# NuPrism_MCPMT_-_ADA4945-1_and_Filter_-_R.net
KiCad netlist of a schematic drawn in Altium Designer
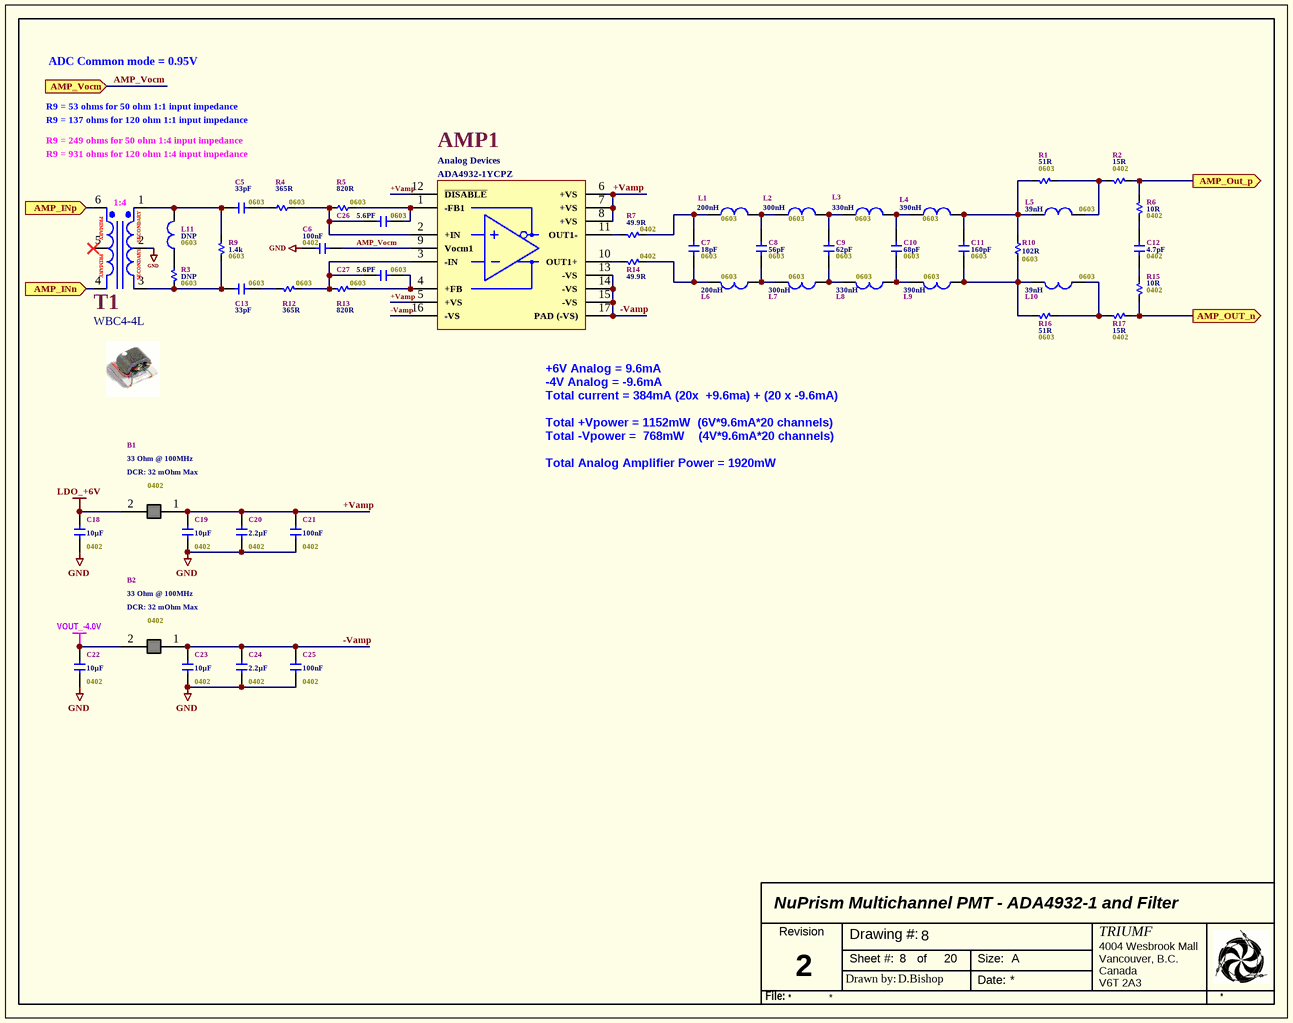
[diagram p0: NuPrism_MCPMT - ADA4945-1 and Filter - Rev2.SchDoc]

(export (version "E")
  (design (tool "Eeschema 10.0.6"))
  (components
    (comp (ref "AMP1")
      (value "ADA4932-1YCPZ")
      (footprint "QFN50P300X300X100-16N_ALT")
      (description "High Speed, ±0.1 µV/˚C Offset Drift, Fully Differential ADC Driver")
      (fields (field (name "MANUFACTURER") "Analog Devices") (field (name "PARTNO") "ADA4932-1YCPZ"))
      (libsource (lib "NuPrism_MCPMT") (part "ADA4932-1YCPZ_ALT"))
    )
    (comp (ref "B1")
      (value "BLM15PX600SN1D")
      (footprint "0402")
      (description "60 Ohms @ 100MHz Ferrite Bead 0402 2.5A")
      (fields
        (field (name "MANUFACTURER") "Murata")
        (field (name "DCR") "32 mOhm Max")
        (field (name "IMPEDANCE @ FREQUENCY") "33 Ohm @ 100MHz")
        (field (name "PACKAGE") "0402")
      )
      (libsource (lib "Clock Distribution Module") (part "Ferrite Bead"))
    )
    (comp (ref "B2")
      (value "BLM15PX600SN1D")
      (footprint "0402")
      (description "60 Ohms @ 100MHz Ferrite Bead 0402 2.5A")
      (fields
        (field (name "MANUFACTURER") "Murata")
        (field (name "DCR") "32 mOhm Max")
        (field (name "IMPEDANCE @ FREQUENCY") "33 Ohm @ 100MHz")
        (field (name "PACKAGE") "0402")
      )
      (libsource (lib "Clock Distribution Module") (part "Ferrite Bead"))
    )
    (comp (ref "C5")
      (value "C0603C330J1GAC7867")
      (footprint "0603")
      (description "33 pF ±5% 100V Ceramic Capacitor C0G, NP0 0603")
      (fields
        (field (name "MANUFACTURER") "KEMET")
        (field (name "CAPACITANCE") "33pF")
        (field (name "PACKAGE") "0603")
        (field (name "VOLTAGE") "100V")
      )
      (libsource (lib "altium-import") (part "root_1_CAP-SMALL_"))
    )
    (comp (ref "C6")
      (value "C0402C104K4RACTU")
      (footprint "0402")
      (description "SMD/SMT 0402 16V 0.1uF X7R 10%")
      (fields
        (field (name "MANUFACTURER") "Kemet")
        (field (name "CAPACITANCE") "100nF")
        (field (name "PACKAGE") "0402")
        (field (name "VOLTAGE") "16V")
      )
      (libsource (lib "NuPrism_MCPMT") (part "CAP-SMALL"))
    )
    (comp (ref "C7")
      (value "CC0603JPNPO9BN180")
      (footprint "0603")
      (description "18 pF ±5% 50V Ceramic Capacitor C0G, NP0 0603")
      (fields
        (field (name "CAPACITANCE") "18pF")
        (field (name "PACKAGE") "0603")
        (field (name "MANUFACTURER") "Yageo")
        (field (name "VOLTAGE") "50V")
      )
      (libsource (lib "") (part "root_2_CAP-SMALL__1"))
    )
    (comp (ref "C8")
      (value "C0603C560J5GAC7867")
      (footprint "0603")
      (description "56 pF ±5% 50V Ceramic Capacitor C0G, NP0 0603 (1608 Metric)")
      (fields
        (field (name "MANUFACTURER") "KEMET")
        (field (name "CAPACITANCE") "56pF")
        (field (name "PACKAGE") "0603")
        (field (name "VOLTAGE") "50V")
      )
      (libsource (lib "") (part "root_2_CAP-SMALL__1"))
    )
    (comp (ref "C9")
      (value "CC0603JRNPO9BN620")
      (footprint "0603")
      (description "62 pF ±5% 50V Ceramic Capacitor C0G, NP0 0603 (1608 Metric)")
      (fields
        (field (name "MANUFACTURER") "YAGEO")
        (field (name "CAPACITANCE") "62pF")
        (field (name "PACKAGE") "0603")
        (field (name "VOLTAGE") "50V")
      )
      (libsource (lib "") (part "root_2_CAP-SMALL__1"))
    )
    (comp (ref "C10")
      (value "CC0603JRNPO9BN680")
      (footprint "0603")
      (description "CAP CER 68PF 50V C0G/NPO 0603 (1608 Metric)")
      (fields
        (field (name "CAPACITANCE") "68pF")
        (field (name "PACKAGE") "0603")
        (field (name "MANUFACTURER") "Yageo")
        (field (name "VOLTAGE") "50V")
      )
      (libsource (lib "") (part "root_2_CAP-SMALL__1"))
    )
    (comp (ref "C11")
      (value "CC0603JRNPO9BN161")
      (footprint "0603")
      (description "160 pF ±5% 50V Ceramic Capacitor C0G, NP0 0603 (1608 Metric)")
      (fields
        (field (name "MANUFACTURER") "YAGEO")
        (field (name "CAPACITANCE") "160pF")
        (field (name "PACKAGE") "0603")
        (field (name "VOLTAGE") "50V")
      )
      (libsource (lib "") (part "root_2_CAP-SMALL__1"))
    )
    (comp (ref "C12")
      (value "CC0402BRNPO9BN4R7")
      (footprint "0402")
      (description "4.7pF ±0.1pF 50V Ceramic Capacitor C0G, NP0 0402")
      (fields
        (field (name "MANUFACTURER") "Yageo")
        (field (name "CAPACITANCE") "4.7pF")
        (field (name "PACKAGE") "0402")
        (field (name "VOLTAGE") "50V")
      )
      (libsource (lib "") (part "root_2_CAP-SMALL__1"))
    )
    (comp (ref "C13")
      (value "C0603C330J1GAC7867")
      (footprint "0603")
      (description "33 pF ±5% 100V Ceramic Capacitor C0G, NP0 0603")
      (fields
        (field (name "MANUFACTURER") "KEMET")
        (field (name "CAPACITANCE") "33pF")
        (field (name "PACKAGE") "0603")
        (field (name "VOLTAGE") "100V")
      )
      (libsource (lib "altium-import") (part "root_3_mirrored_CAP-SMALL_"))
    )
    (comp (ref "C18")
      (value "CL05A106MQ5NRNC")
      (footprint "0402")
      (description "10 µF ±20% 6.3V Ceramic Capacitor X5R 0402 (1005 Metric)")
      (fields
        (field (name "CAPACITANCE") "10µF")
        (field (name "PACKAGE") "0402")
        (field (name "MANUFACTURER") "Samsung Electro-Mechanics")
        (field (name "VOLTAGE") "6.3V")
      )
      (libsource (lib "altium-import") (part "root_2_CAP-SMALL_"))
    )
    (comp (ref "C19")
      (value "CL05A106MQ5NRNC")
      (footprint "0402")
      (description "10 µF ±20% 6.3V Ceramic Capacitor X5R 0402 (1005 Metric)")
      (fields
        (field (name "CAPACITANCE") "10µF")
        (field (name "PACKAGE") "0402")
        (field (name "MANUFACTURER") "Samsung Electro-Mechanics")
        (field (name "VOLTAGE") "6.3V")
      )
      (libsource (lib "altium-import") (part "root_2_CAP-SMALL_"))
    )
    (comp (ref "C20")
      (value "TMK105CBJ225KV-F")
      (footprint "0402")
      (description "SMD/SMT 0402 25V 2.2uF 10% X5R")
      (fields
        (field (name "MANUFACTURER") "Taiyo Yuden")
        (field (name "CAPACITANCE") "2.2µF")
        (field (name "PACKAGE") "0402")
        (field (name "VOLTAGE") "25V")
      )
      (libsource (lib "altium-import") (part "root_0_CAP-SMALL_"))
    )
    (comp (ref "C21")
      (value "C0402C104K4RACTU")
      (footprint "0402")
      (description "SMD/SMT 0402 16V 0.1uF X7R 10%")
      (fields
        (field (name "MANUFACTURER") "Kemet")
        (field (name "CAPACITANCE") "100nF")
        (field (name "PACKAGE") "0402")
        (field (name "VOLTAGE") "16V")
      )
      (libsource (lib "NuPrism_MCPMT") (part "CAP-SMALL"))
    )
    (comp (ref "C22")
      (value "CL05A106MQ5NRNC")
      (footprint "0402")
      (description "10 µF ±20% 6.3V Ceramic Capacitor X5R 0402 (1005 Metric)")
      (fields
        (field (name "CAPACITANCE") "10µF")
        (field (name "PACKAGE") "0402")
        (field (name "MANUFACTURER") "Samsung Electro-Mechanics")
        (field (name "VOLTAGE") "6.3V")
      )
      (libsource (lib "altium-import") (part "root_2_CAP-SMALL_"))
    )
    (comp (ref "C23")
      (value "CL05A106MQ5NRNC")
      (footprint "0402")
      (description "10 µF ±20% 6.3V Ceramic Capacitor X5R 0402 (1005 Metric)")
      (fields
        (field (name "CAPACITANCE") "10µF")
        (field (name "PACKAGE") "0402")
        (field (name "MANUFACTURER") "Samsung Electro-Mechanics")
        (field (name "VOLTAGE") "6.3V")
      )
      (libsource (lib "altium-import") (part "root_2_CAP-SMALL_"))
    )
    (comp (ref "C24")
      (value "TMK105CBJ225KV-F")
      (footprint "0402")
      (description "SMD/SMT 0402 25V 2.2uF 10% X5R")
      (fields
        (field (name "MANUFACTURER") "Taiyo Yuden")
        (field (name "CAPACITANCE") "2.2µF")
        (field (name "PACKAGE") "0402")
        (field (name "VOLTAGE") "25V")
      )
      (libsource (lib "altium-import") (part "root_0_CAP-SMALL_"))
    )
    (comp (ref "C25")
      (value "C0402C104K4RACTU")
      (footprint "0402")
      (description "SMD/SMT 0402 16V 0.1uF X7R 10%")
      (fields
        (field (name "MANUFACTURER") "Kemet")
        (field (name "CAPACITANCE") "100nF")
        (field (name "PACKAGE") "0402")
        (field (name "VOLTAGE") "16V")
      )
      (libsource (lib "NuPrism_MCPMT") (part "CAP-SMALL"))
    )
    (comp (ref "C26")
      (value "06035A5R6JAT2A")
      (footprint "0603")
      (description "5.6 pF ±5% 50V Ceramic Capacitor C0G, NP0 0603")
      (fields
        (field (name "MANUFACTURER") "KYOCERA AVX")
        (field (name "CAPACITANCE") "5.6PF")
        (field (name "PACKAGE") "0603")
        (field (name "VOLTAGE") "50V")
      )
      (libsource (lib "altium-import") (part "root_3_CAP-SMALL_"))
    )
    (comp (ref "C27")
      (value "06035A5R6JAT2A")
      (footprint "0603")
      (description "5.6 pF ±5% 50V Ceramic Capacitor C0G, NP0 0603")
      (fields
        (field (name "MANUFACTURER") "KYOCERA AVX")
        (field (name "CAPACITANCE") "5.6PF")
        (field (name "PACKAGE") "0603")
        (field (name "VOLTAGE") "50V")
      )
      (libsource (lib "altium-import") (part "root_3_CAP-SMALL_"))
    )
    (comp (ref "L1")
      (value "LQW18ANR20J8ZD")
      (footprint "NumPrism Mutichannel PMT:0603 - Inductor")
      (description "200 nH Unshielded Wirewound Inductor 120 mA 2.40Ohm Max 0603")
      (fields
        (field (name "PACKAGE") "0603")
        (field (name "INDUCTANCE") "200nH")
        (field (name "MANUFACTURER") "Murata Electronics")
        (field (name "PARTNO") "LQW18ANR20G00D")
      )
      (libsource (lib "NuPrism - mPMT") (part "Inductor1"))
    )
    (comp (ref "L2")
      (value "LQW18ANR30G80D")
      (footprint "0603 - Inductor")
      (description "300 nH Unshielded Wirewound Inductor 220 mA 3.12Ohm Max 0603")
      (fields
        (field (name "PACKAGE") "0603")
        (field (name "INDUCTANCE") "300nH")
        (field (name "MANUFACTURER") "Coilcraft")
        (field (name "PARTNO") "LQW18ANR30G8ZD")
      )
      (libsource (lib "NuPrism - mPMT") (part "Inductor1"))
    )
    (comp (ref "L3")
      (value "LQW18CNR33J00D")
      (footprint "0603 - Inductor")
      (description "330 nH Unshielded Drum Core, Wirewound Inductor 630 mA 250mOhm Max 0603")
      (fields
        (field (name "PACKAGE") "0603")
        (field (name "INDUCTANCE") "330nH")
        (field (name "MANUFACTURER") "Murata Electronics")
      )
      (libsource (lib "NuPrism - mPMT") (part "Inductor1"))
    )
    (comp (ref "L4")
      (value "MLJ1608WR39JT000")
      (footprint "0603 - inductor")
      (description "390 nH Shielded Multilayer Inductor 450 mA 364mOhm Max 0603 (1608 Metric)")
      (fields
        (field (name "PACKAGE") "0603")
        (field (name "INDUCTANCE") "390nH")
        (field (name "MANUFACTURER") "TDK Corporation")
      )
      (libsource (lib "NuPrism - mPMT") (part "Inductor1"))
    )
    (comp (ref "L5")
      (value "LQW18AN39NJ00D")
      (footprint "0603 - Inductor_2")
      (description "39 nH Unshielded Wirewound Inductor 400 mA 260mOhm Max 0603 (1608 Metric)")
      (fields
        (field (name "PACKAGE") "0603")
        (field (name "INDUCTANCE") "39nH")
        (field (name "MANUFACTURER") "Murata Electronics")
      )
      (libsource (lib "NuPrism - mPMT") (part "Inductor1"))
    )
    (comp (ref "L6")
      (value "LQW18ANR20J8ZD")
      (footprint "0603 - Inductor")
      (description "200 nH Unshielded Wirewound Inductor 120 mA 2.40Ohm Max 0603")
      (fields
        (field (name "PACKAGE") "0603")
        (field (name "INDUCTANCE") "200nH")
        (field (name "MANUFACTURER") "Murata Electronics")
        (field (name "PARTNO") "LQW18ANR20G00D")
      )
      (libsource (lib "") (part "Inductor1_1"))
    )
    (comp (ref "L7")
      (value "LQW18ANR30G80D")
      (footprint "0603 - Inductor")
      (description "300 nH Unshielded Wirewound Inductor 220 mA 3.12Ohm Max 0603")
      (fields
        (field (name "PACKAGE") "0603")
        (field (name "INDUCTANCE") "300nH")
        (field (name "MANUFACTURER") "Coilcraft")
        (field (name "PARTNO") "LQW18ANR30G8ZD")
      )
      (libsource (lib "") (part "Inductor1_1"))
    )
    (comp (ref "L8")
      (value "LQW18CNR33J00D")
      (footprint "0603 - Inductor")
      (description "330 nH Unshielded Drum Core, Wirewound Inductor 630 mA 250mOhm Max 0603")
      (fields
        (field (name "PACKAGE") "0603")
        (field (name "INDUCTANCE") "330nH")
        (field (name "MANUFACTURER") "Murata Electronics")
      )
      (libsource (lib "") (part "Inductor1_1"))
    )
    (comp (ref "L9")
      (value "MLJ1608WR39JT000")
      (footprint "0603 - inductor")
      (description "390 nH Shielded Multilayer Inductor 450 mA 364mOhm Max 0603 (1608 Metric)")
      (fields
        (field (name "PACKAGE") "0603")
        (field (name "INDUCTANCE") "390nH")
        (field (name "MANUFACTURER") "TDK Corporation")
      )
      (libsource (lib "") (part "Inductor1_1"))
    )
    (comp (ref "L10")
      (value "LQW18AN39NJ00D")
      (footprint "0603 - Inductor_2")
      (description "39 nH Unshielded Wirewound Inductor 400 mA 260mOhm Max 0603 (1608 Metric)")
      (fields
        (field (name "PACKAGE") "0603")
        (field (name "INDUCTANCE") "39nH")
        (field (name "MANUFACTURER") "Murata Electronics")
      )
      (libsource (lib "") (part "Inductor1_1"))
    )
    (comp (ref "L11")
      (value "~")
      (footprint "0603 - Inductor")
      (description "Do not put")
      (fields (field (name "PACKAGE") "0603") (field (name "INDUCTANCE") "DNP"))
      (libsource (lib "NuPrism - mPMT") (part "Inductor1"))
    )
    (comp (ref "R1")
      (value "RC0603FR-0751RL")
      (footprint "0603")
      (description "Thick Film Resistors - SMD 51 OHM 1%")
      (fields
        (field (name "MANUFACTURER") "Yageo")
        (field (name "RESISTANCE") "51R")
        (field (name "PACKAGE") "0603")
      )
      (libsource (lib "NuPrism - mPMT") (part "RES-TINY"))
    )
    (comp (ref "R2")
      (value "RMCF0402FT15R0")
      (footprint "0402")
      (description "15 Ohms ±1% 0.063W, 1/16W Chip Resistor 0402 (1005 Metric)")
      (fields
        (field (name "MANUFACTURER") "Stackpole Electronics Inc")
        (field (name "RESISTANCE") "15R")
        (field (name "PACKAGE") "0402")
      )
      (libsource (lib "NuPrism - mPMT") (part "RES-TINY"))
    )
    (comp (ref "R3")
      (value "~")
      (footprint "0603")
      (description "Do not put")
      (fields
        (field (name "MANUFACTURER") "Yageo")
        (field (name "PARTNO") "RT0603BRD07820RL")
        (field (name "RESISTANCE") "DNP")
        (field (name "PACKAGE") "0603")
      )
      (libsource (lib "NuPrism - mPMT") (part "RES-TINY"))
    )
    (comp (ref "R4")
      (value "ERJ-PB3B3650V")
      (footprint "0603")
      (description "Thick Film Resistors - SMD 0603 Anti-Surge Res. 0.1%, 365ohm")
      (fields
        (field (name "MANUFACTURER") "Panasonic")
        (field (name "RESISTANCE") "365R")
        (field (name "PACKAGE") "0603")
      )
      (libsource (lib "NuPrism - mPMT") (part "RES-TINY"))
    )
    (comp (ref "R5")
      (value "RT0603BRD07820RL")
      (footprint "0603")
      (description "820 Ohms ±0.1% 0.1W, 1/10W Chip Resistor 0603 (1608 Metric) Thin Film")
      (fields
        (field (name "MANUFACTURER") "Yageo")
        (field (name "RESISTANCE") "820R")
        (field (name "PACKAGE") "0603")
      )
      (libsource (lib "NuPrism - mPMT") (part "RES-TINY"))
    )
    (comp (ref "R6")
      (value "RC0402FR-0710RL")
      (footprint "0402")
      (description "10 Ohms ±1% 0.063W, 1/16W Chip Resistor 0402")
      (fields
        (field (name "MANUFACTURER") "Yageo")
        (field (name "RESISTANCE") "10R")
        (field (name "PACKAGE") "0402")
        (field (name "VOLTAGE") "50V")
      )
      (libsource (lib "") (part "RES-TINY_2"))
    )
    (comp (ref "R7")
      (value "RMCF0402FT49R9")
      (footprint "0402")
      (description "49.9 Ohms ±1% 0.063W, 1/16W Chip Resistor 0402 (1005 Metric)")
      (fields
        (field (name "MANUFACTURER") "Stackpole Electronics Inc")
        (field (name "RESISTANCE") "49.9R")
        (field (name "PACKAGE") "0402")
      )
      (libsource (lib "NuPrism - mPMT") (part "RES-TINY"))
    )
    (comp (ref "R9")
      (value "RC0603FR-101K4L")
      (footprint "0603")
      (description "1.4 kOhms ±1% 0.1W, 1/10W Chip Resistor 0603 (1608 Metric) Thick Film")
      (fields
        (field (name "MANUFACTURER") "Stackpole")
        (field (name "PARTNO") "RC0603FR-101K2L")
        (field (name "RESISTANCE") "1.4k")
        (field (name "PACKAGE") "0603")
      )
      (libsource (lib "NuPrism - mPMT") (part "RES-TINY"))
    )
    (comp (ref "R10")
      (value "RC0603FR-07102RL")
      (footprint "0603")
      (description "102 Ohms ±1% 0.1W, 1/10W Chip Resistor 0603")
      (fields
        (field (name "MANUFACTURER") "Yageo")
        (field (name "RESISTANCE") "102R")
        (field (name "PACKAGE") "0603")
      )
      (libsource (lib "NuPrism - mPMT") (part "RES-TINY"))
    )
    (comp (ref "R12")
      (value "ERJ-PB3B3650V")
      (footprint "0603")
      (description "Thick Film Resistors - SMD 0603 Anti-Surge Res. 0.1%, 365ohm")
      (fields
        (field (name "MANUFACTURER") "Panasonic")
        (field (name "RESISTANCE") "365R")
        (field (name "PACKAGE") "0603")
      )
      (libsource (lib "NuPrism - mPMT") (part "RES-TINY"))
    )
    (comp (ref "R13")
      (value "RT0603BRD07820RL")
      (footprint "0603")
      (description "820 Ohms ±0.1% 0.1W, 1/10W Chip Resistor 0603 (1608 Metric) Thin Film")
      (fields
        (field (name "MANUFACTURER") "Yageo")
        (field (name "RESISTANCE") "820R")
        (field (name "PACKAGE") "0603")
      )
      (libsource (lib "NuPrism - mPMT") (part "RES-TINY"))
    )
    (comp (ref "R14")
      (value "RMCF0402FT49R9")
      (footprint "0402")
      (description "49.9 Ohms ±1% 0.063W, 1/16W Chip Resistor 0402 (1005 Metric)")
      (fields
        (field (name "MANUFACTURER") "Stackpole Electronics Inc")
        (field (name "RESISTANCE") "49.9R")
        (field (name "PACKAGE") "0402")
      )
      (libsource (lib "NuPrism - mPMT") (part "RES-TINY"))
    )
    (comp (ref "R15")
      (value "RC0402FR-0710RL")
      (footprint "0402")
      (description "10 Ohms ±1% 0.063W, 1/16W Chip Resistor 0402")
      (fields
        (field (name "MANUFACTURER") "Yageo")
        (field (name "RESISTANCE") "10R")
        (field (name "PACKAGE") "0402")
        (field (name "VOLTAGE") "50V")
      )
      (libsource (lib "") (part "RES-TINY_1"))
    )
    (comp (ref "R16")
      (value "RC0603FR-0751RL")
      (footprint "0603")
      (description "Thick Film Resistors - SMD 51 OHM 1%")
      (fields
        (field (name "MANUFACTURER") "Yageo")
        (field (name "RESISTANCE") "51R")
        (field (name "PACKAGE") "0603")
      )
      (libsource (lib "NuPrism - mPMT") (part "RES-TINY"))
    )
    (comp (ref "R17")
      (value "RMCF0402FT15R0")
      (footprint "0402")
      (description "15 Ohms ±1% 0.063W, 1/16W Chip Resistor 0402 (1005 Metric)")
      (fields
        (field (name "MANUFACTURER") "Stackpole Electronics Inc")
        (field (name "RESISTANCE") "15R")
        (field (name "PACKAGE") "0402")
      )
      (libsource (lib "NuPrism - mPMT") (part "RES-TINY"))
    )
    (comp (ref "T1")
      (value "WBC4-4L")
      (footprint "WBC4-4WL")
      (description "Audio Transformers / Signal Transformers WBC SMT Mini Wdebnd 1:4 0.250-800 MHz")
      (fields (field (name "MANUFACTURER") "Coilcraft"))
      (libsource (lib "NuPrism_MCPMT") (part "WBC4-4L"))
    )
  )
  (nets
    (net (code "1") (name "/+Vamp") (class "Default")
      (node (ref "AMP1") (pin "12") (pinfunction "~{DISABLE}_12") (pintype "passive"))
      (node (ref "AMP1") (pin "5") (pinfunction "+VS_5") (pintype "power_in"))
      (node (ref "AMP1") (pin "6") (pinfunction "+VS_6") (pintype "power_in"))
      (node (ref "AMP1") (pin "7") (pinfunction "+VS_7") (pintype "power_in"))
      (node (ref "AMP1") (pin "8") (pinfunction "+VS_8") (pintype "power_in"))
      (node (ref "B1") (pin "1") (pinfunction "1_1") (pintype "passive"))
      (node (ref "C19") (pin "2") (pintype "passive"))
      (node (ref "C20") (pin "1") (pintype "passive"))
      (node (ref "C21") (pin "1") (pintype "passive"))
    )
    (net (code "2") (name "/-Vamp") (class "Default")
      (node (ref "AMP1") (pin "13") (pinfunction "-VS_13") (pintype "power_in"))
      (node (ref "AMP1") (pin "14") (pinfunction "-VS_14") (pintype "power_in"))
      (node (ref "AMP1") (pin "15") (pinfunction "-VS_15") (pintype "power_in"))
      (node (ref "AMP1") (pin "16") (pinfunction "-VS_16") (pintype "power_in"))
      (node (ref "AMP1") (pin "17") (pinfunction "PAD_(-VS)_17") (pintype "power_in"))
      (node (ref "B2") (pin "1") (pinfunction "1_1") (pintype "passive"))
      (node (ref "C23") (pin "2") (pintype "passive"))
      (node (ref "C24") (pin "1") (pintype "passive"))
      (node (ref "C25") (pin "1") (pintype "passive"))
    )
    (net (code "3") (name "/AMP_INn") (class "Default")
      (node (ref "T1") (pin "4") (pinfunction "Pri-_4") (pintype "passive"))
    )
    (net (code "4") (name "/AMP_INp") (class "Default")
      (node (ref "T1") (pin "6") (pinfunction "Pri+_6") (pintype "passive"))
    )
    (net (code "5") (name "/AMP_OUT_n") (class "Default")
      (node (ref "R15") (pin "1") (pintype "output"))
      (node (ref "R17") (pin "2") (pintype "passive"))
    )
    (net (code "6") (name "/AMP_Out_p") (class "Default")
      (node (ref "R2") (pin "2") (pintype "passive"))
      (node (ref "R6") (pin "2") (pintype "output"))
    )
    (net (code "7") (name "/AMP_Vocm") (class "Default")
      (node (ref "AMP1") (pin "9") (pinfunction "Vocm1_9") (pintype "passive"))
      (node (ref "C6") (pin "2") (pintype "passive"))
    )
    (net (code "8") (name "GND") (class "Default")
      (node (ref "C18") (pin "1") (pintype "passive"))
      (node (ref "C19") (pin "1") (pintype "passive"))
      (node (ref "C20") (pin "2") (pintype "passive"))
      (node (ref "C21") (pin "2") (pintype "passive"))
      (node (ref "C22") (pin "1") (pintype "passive"))
      (node (ref "C23") (pin "1") (pintype "passive"))
      (node (ref "C24") (pin "2") (pintype "passive"))
      (node (ref "C25") (pin "2") (pintype "passive"))
      (node (ref "C6") (pin "1") (pintype "passive"))
      (node (ref "T1") (pin "2") (pinfunction "SecCT_2") (pintype "passive"))
    )
    (net (code "9") (name "LDO_+6V") (class "Default")
      (node (ref "B1") (pin "2") (pinfunction "2_2") (pintype "passive"))
      (node (ref "C18") (pin "2") (pintype "passive"))
    )
    (net (code "10") (name "Net-(AMP1-+FB)") (class "Default")
      (node (ref "AMP1") (pin "4") (pinfunction "+FB_4") (pintype "passive"))
      (node (ref "C27") (pin "1") (pintype "passive"))
      (node (ref "R13") (pin "1") (pintype "passive"))
    )
    (net (code "11") (name "Net-(AMP1-+IN)") (class "Default")
      (node (ref "AMP1") (pin "2") (pinfunction "+IN_2") (pintype "passive"))
      (node (ref "C26") (pin "2") (pintype "passive"))
      (node (ref "R4") (pin "1") (pintype "passive"))
      (node (ref "R5") (pin "2") (pintype "passive"))
    )
    (net (code "12") (name "Net-(AMP1--FB1)") (class "Default")
      (node (ref "AMP1") (pin "1") (pinfunction "-FB1_1") (pintype "passive"))
      (node (ref "C26") (pin "1") (pintype "passive"))
      (node (ref "R5") (pin "1") (pintype "passive"))
    )
    (net (code "13") (name "Net-(AMP1--IN)") (class "Default")
      (node (ref "AMP1") (pin "3") (pinfunction "-IN_3") (pintype "passive"))
      (node (ref "C27") (pin "2") (pintype "passive"))
      (node (ref "R12") (pin "1") (pintype "passive"))
      (node (ref "R13") (pin "2") (pintype "passive"))
    )
    (net (code "14") (name "Net-(AMP1-OUT1+)") (class "Default")
      (node (ref "AMP1") (pin "10") (pinfunction "OUT1+_10") (pintype "passive"))
      (node (ref "R14") (pin "2") (pintype "passive"))
    )
    (net (code "15") (name "Net-(AMP1-OUT1-)") (class "Default")
      (node (ref "AMP1") (pin "11") (pinfunction "OUT1-_11") (pintype "passive"))
      (node (ref "R7") (pin "2") (pintype "passive"))
    )
    (net (code "16") (name "Net-(C5-Pad2)") (class "Default")
      (node (ref "C5") (pin "2") (pintype "passive"))
      (node (ref "R4") (pin "2") (pintype "passive"))
    )
    (net (code "17") (name "Net-(C7-Pad1)") (class "Default")
      (node (ref "C7") (pin "1") (pintype "passive"))
      (node (ref "L6") (pin "1") (pinfunction "1_1") (pintype "passive"))
      (node (ref "R14") (pin "1") (pintype "passive"))
    )
    (net (code "18") (name "Net-(C7-Pad2)") (class "Default")
      (node (ref "C7") (pin "2") (pintype "passive"))
      (node (ref "L1") (pin "1") (pinfunction "1_1") (pintype "passive"))
      (node (ref "R7") (pin "1") (pintype "passive"))
    )
    (net (code "19") (name "Net-(C8-Pad1)") (class "Default")
      (node (ref "C8") (pin "1") (pintype "passive"))
      (node (ref "L6") (pin "2") (pinfunction "2_2") (pintype "passive"))
      (node (ref "L7") (pin "1") (pinfunction "1_1") (pintype "passive"))
    )
    (net (code "20") (name "Net-(C8-Pad2)") (class "Default")
      (node (ref "C8") (pin "2") (pintype "passive"))
      (node (ref "L1") (pin "2") (pinfunction "2_2") (pintype "passive"))
      (node (ref "L2") (pin "1") (pinfunction "1_1") (pintype "passive"))
    )
    (net (code "21") (name "Net-(C9-Pad1)") (class "Default")
      (node (ref "C9") (pin "1") (pintype "passive"))
      (node (ref "L7") (pin "2") (pinfunction "2_2") (pintype "passive"))
      (node (ref "L8") (pin "1") (pinfunction "1_1") (pintype "passive"))
    )
    (net (code "22") (name "Net-(C9-Pad2)") (class "Default")
      (node (ref "C9") (pin "2") (pintype "passive"))
      (node (ref "L2") (pin "2") (pinfunction "2_2") (pintype "passive"))
      (node (ref "L3") (pin "1") (pinfunction "1_1") (pintype "passive"))
    )
    (net (code "23") (name "Net-(C10-Pad1)") (class "Default")
      (node (ref "C10") (pin "1") (pintype "passive"))
      (node (ref "L8") (pin "2") (pinfunction "2_2") (pintype "passive"))
      (node (ref "L9") (pin "1") (pinfunction "1_1") (pintype "passive"))
    )
    (net (code "24") (name "Net-(C10-Pad2)") (class "Default")
      (node (ref "C10") (pin "2") (pintype "passive"))
      (node (ref "L3") (pin "2") (pinfunction "2_2") (pintype "passive"))
      (node (ref "L4") (pin "1") (pinfunction "1_1") (pintype "passive"))
    )
    (net (code "25") (name "Net-(C11-Pad1)") (class "Default")
      (node (ref "C11") (pin "1") (pintype "passive"))
      (node (ref "L10") (pin "1") (pinfunction "1_1") (pintype "passive"))
      (node (ref "L9") (pin "2") (pinfunction "2_2") (pintype "passive"))
      (node (ref "R10") (pin "2") (pintype "passive"))
      (node (ref "R16") (pin "1") (pintype "passive"))
    )
    (net (code "26") (name "Net-(C11-Pad2)") (class "Default")
      (node (ref "C11") (pin "2") (pintype "passive"))
      (node (ref "L4") (pin "2") (pinfunction "2_2") (pintype "passive"))
      (node (ref "L5") (pin "1") (pinfunction "1_1") (pintype "passive"))
      (node (ref "R1") (pin "1") (pintype "passive"))
      (node (ref "R10") (pin "1") (pintype "passive"))
    )
    (net (code "27") (name "Net-(C12-Pad1)") (class "Default")
      (node (ref "C12") (pin "1") (pintype "passive"))
      (node (ref "R15") (pin "2") (pintype "passive"))
    )
    (net (code "28") (name "Net-(C12-Pad2)") (class "Default")
      (node (ref "C12") (pin "2") (pintype "passive"))
      (node (ref "R6") (pin "1") (pintype "passive"))
    )
    (net (code "29") (name "Net-(C13-Pad2)") (class "Default")
      (node (ref "C13") (pin "2") (pintype "passive"))
      (node (ref "R12") (pin "2") (pintype "passive"))
    )
    (net (code "30") (name "Net-(L5-Pad2)") (class "Default")
      (node (ref "L5") (pin "2") (pinfunction "2_2") (pintype "passive"))
      (node (ref "R1") (pin "2") (pintype "passive"))
      (node (ref "R2") (pin "1") (pintype "passive"))
    )
    (net (code "31") (name "Net-(L10-Pad2)") (class "Default")
      (node (ref "L10") (pin "2") (pinfunction "2_2") (pintype "passive"))
      (node (ref "R16") (pin "2") (pintype "passive"))
      (node (ref "R17") (pin "1") (pintype "passive"))
    )
    (net (code "32") (name "Net-(L11-Pad1)") (class "Default")
      (node (ref "L11") (pin "1") (pinfunction "1_1") (pintype "passive"))
      (node (ref "R3") (pin "1") (pintype "passive"))
    )
    (net (code "33") (name "Net-(T1-Sec+)") (class "Default")
      (node (ref "C5") (pin "1") (pintype "passive"))
      (node (ref "L11") (pin "2") (pinfunction "2_2") (pintype "passive"))
      (node (ref "R9") (pin "1") (pintype "passive"))
      (node (ref "T1") (pin "1") (pinfunction "Sec+_1") (pintype "passive"))
    )
    (net (code "34") (name "Net-(T1-Sec-)") (class "Default")
      (node (ref "C13") (pin "1") (pintype "passive"))
      (node (ref "R3") (pin "2") (pintype "passive"))
      (node (ref "R9") (pin "2") (pintype "passive"))
      (node (ref "T1") (pin "3") (pinfunction "Sec-_3") (pintype "passive"))
    )
    (net (code "35") (name "VOUT_-4.0V") (class "Default")
      (node (ref "B2") (pin "2") (pinfunction "2_2") (pintype "passive"))
      (node (ref "C22") (pin "2") (pintype "passive"))
    )
    (net (code "36") (name "unconnected-(T1-PriCT-Pad5)") (class "Default")
      (node (ref "T1") (pin "5") (pinfunction "PriCT_5") (pintype "passive+no_connect"))
    )
  )
)
